# DRV8848.net
KiCad netlist of a schematic drawn in EAGLE
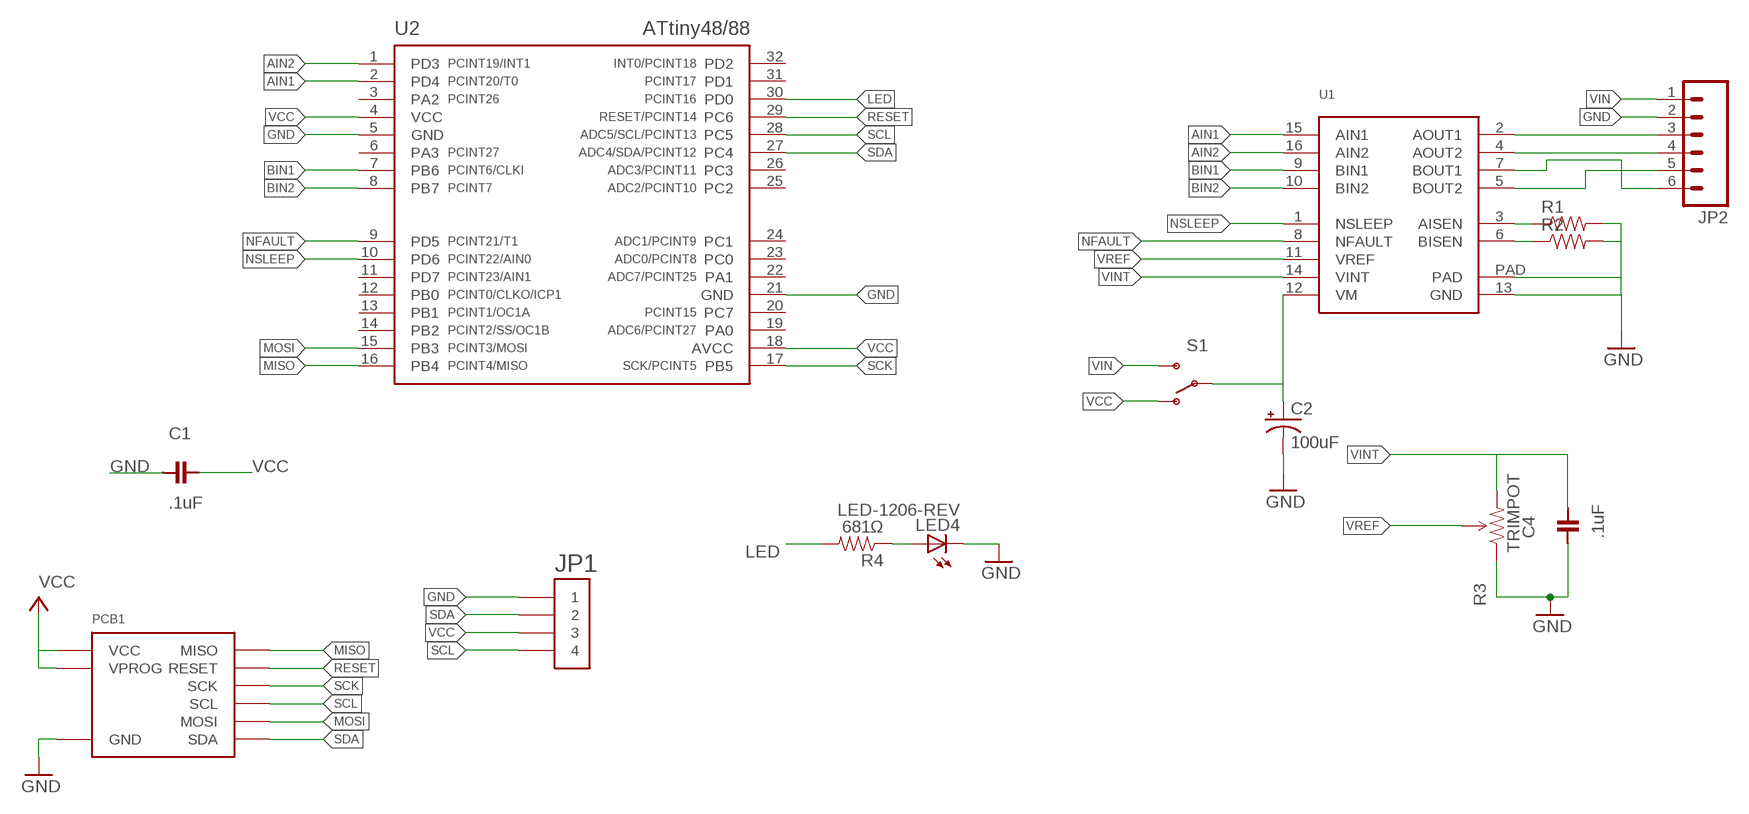
[diagram p0: schematic, sheet 1]

(export (version "E")
  (design (tool "Eeschema 10.0.6"))
  (components
    (comp (ref "C1")
      (value ".1uF")
      (footprint "eagle-import:0603")
      (fields (field (name "PARTNUM") "C0603C104K5RACTU"))
      (libsource (lib "eagle-import") (part "CAPACITOR-.1UF"))
    )
    (comp (ref "C2")
      (value "100uF")
      (footprint "eagle-import:PANASONIC_D")
      (libsource (lib "eagle-import") (part "CAP_POLD"))
    )
    (comp (ref "C4")
      (value ".1uF")
      (footprint "eagle-import:0603")
      (fields (field (name "PARTNUM") "C0603C104K5RACTU"))
      (libsource (lib "eagle-import") (part "CAPACITOR-.1UF"))
    )
    (comp (ref "JP1")
      (value "HEADER-1X4-AMPMODU")
      (footprint "eagle-import:AMPMODU-4P")
      (libsource (lib "eagle-import") (part "HEADER-1X4-AMPMODU"))
    )
    (comp (ref "JP2")
      (value "M063.5MM-6")
      (footprint "eagle-import:SCREWTERMINAL-3.5MM-6")
      (libsource (lib "eagle-import") (part "M063.5MM-6"))
    )
    (comp (ref "LED4")
      (value "LED-1206-REV")
      (footprint "eagle-import:LED-1206-REV")
      (libsource (lib "eagle-import") (part "LED-1206-REV"))
    )
    (comp (ref "PCB1")
      (value "DEVICE-PCB-TABS")
      (footprint "eagle-import:DEVICE-PCB-TABS")
      (libsource (lib "eagle-import") (part "DEVICE-PCB-TABS"))
    )
    (comp (ref "R1")
      (value "RESISTOR-0603")
      (footprint "eagle-import:0603")
      (libsource (lib "eagle-import") (part "RESISTOR-0603"))
    )
    (comp (ref "R2")
      (value "RESISTOR-0603")
      (footprint "eagle-import:0603")
      (libsource (lib "eagle-import") (part "RESISTOR-0603"))
    )
    (comp (ref "R3")
      (value "TRIMPOT")
      (footprint "eagle-import:TRIMPOT-5MM-V2")
      (libsource (lib "eagle-import") (part "TRIMPOT"))
    )
    (comp (ref "R4")
      (value "681Ω")
      (footprint "eagle-import:0603")
      (fields (field (name "PARTNUM") "ERJ-3EKF6810V"))
      (libsource (lib "eagle-import") (part "RESISTOR-681Ω"))
    )
    (comp (ref "S1")
      (value "SWITCH-SPDTPTH")
      (footprint "eagle-import:SWITCH-SPDT")
      (libsource (lib "eagle-import") (part "SWITCH-SPDTPTH"))
    )
    (comp (ref "U1")
      (value "DRV8848")
      (footprint "eagle-import:HTSSOP-16")
      (libsource (lib "eagle-import") (part "DRV8848"))
    )
    (comp (ref "U2")
      (value "ATTINY48/88-TQFP")
      (footprint "eagle-import:TQFP-32")
      (libsource (lib "eagle-import") (part "ATTINY48/88-TQFP"))
    )
  )
  (nets
    (net (code "1") (name "AIN1") (class "Default")
      (node (ref "U1") (pin "15") (pinfunction "AIN1_15") (pintype "bidirectional"))
      (node (ref "U2") (pin "2") (pinfunction "PD4_2") (pintype "bidirectional"))
    )
    (net (code "2") (name "AIN2") (class "Default")
      (node (ref "U1") (pin "16") (pinfunction "AIN2_16") (pintype "bidirectional"))
      (node (ref "U2") (pin "1") (pinfunction "PD3_1") (pintype "bidirectional"))
    )
    (net (code "3") (name "BIN1") (class "Default")
      (node (ref "U1") (pin "9") (pinfunction "BIN1_9") (pintype "bidirectional"))
      (node (ref "U2") (pin "7") (pinfunction "PB6_7") (pintype "bidirectional"))
    )
    (net (code "4") (name "BIN2") (class "Default")
      (node (ref "U1") (pin "10") (pinfunction "BIN2_10") (pintype "bidirectional"))
      (node (ref "U2") (pin "8") (pinfunction "PB7_8") (pintype "bidirectional"))
    )
    (net (code "5") (name "GND") (class "Default")
      (node (ref "C1") (pin "2") (pinfunction "2_2") (pintype "passive"))
      (node (ref "C2") (pin "-") (pinfunction "-_-") (pintype "passive"))
      (node (ref "C4") (pin "2") (pinfunction "2_2") (pintype "passive"))
      (node (ref "JP1") (pin "P$1") (pinfunction "1_P$1") (pintype "bidirectional"))
      (node (ref "JP1") (pin "P$2") (pinfunction "1_P$2") (pintype "bidirectional"))
      (node (ref "JP2") (pin "2") (pinfunction "2_2") (pintype "passive"))
      (node (ref "LED4") (pin "C") (pinfunction "C_C") (pintype "passive"))
      (node (ref "PCB1") (pin "GND") (pinfunction "GND_GND") (pintype "bidirectional"))
      (node (ref "PCB1") (pin "GND1") (pinfunction "GND_GND1") (pintype "bidirectional"))
      (node (ref "R1") (pin "2") (pinfunction "2_2") (pintype "passive"))
      (node (ref "R2") (pin "2") (pinfunction "2_2") (pintype "passive"))
      (node (ref "R3") (pin "A") (pinfunction "CCW_A") (pintype "passive"))
      (node (ref "U1") (pin "13") (pinfunction "GND_13") (pintype "bidirectional"))
      (node (ref "U1") (pin "PAD") (pinfunction "PAD_PAD") (pintype "bidirectional"))
      (node (ref "U2") (pin "21") (pinfunction "GND_21") (pintype "bidirectional"))
      (node (ref "U2") (pin "5") (pinfunction "GND_5") (pintype "bidirectional"))
    )
    (net (code "6") (name "LED") (class "Default")
      (node (ref "R4") (pin "2") (pinfunction "2_2") (pintype "passive"))
      (node (ref "U2") (pin "30") (pinfunction "PD0_30") (pintype "bidirectional"))
    )
    (net (code "7") (name "MISO") (class "Default")
      (node (ref "PCB1") (pin "MISO") (pinfunction "MISO_MISO") (pintype "bidirectional"))
      (node (ref "PCB1") (pin "MISO1") (pinfunction "MISO_MISO1") (pintype "bidirectional"))
      (node (ref "U2") (pin "16") (pinfunction "PB4_16") (pintype "bidirectional"))
    )
    (net (code "8") (name "MOSI") (class "Default")
      (node (ref "PCB1") (pin "MOSI") (pinfunction "MOSI_MOSI") (pintype "bidirectional"))
      (node (ref "PCB1") (pin "MOSI1") (pinfunction "MOSI_MOSI1") (pintype "bidirectional"))
      (node (ref "U2") (pin "15") (pinfunction "PB3_15") (pintype "bidirectional"))
    )
    (net (code "9") (name "NFAULT") (class "Default")
      (node (ref "U1") (pin "8") (pinfunction "NFAULT_8") (pintype "bidirectional"))
      (node (ref "U2") (pin "9") (pinfunction "PD5_9") (pintype "bidirectional"))
    )
    (net (code "10") (name "NSLEEP") (class "Default")
      (node (ref "U1") (pin "1") (pinfunction "NSLEEP_1") (pintype "bidirectional"))
      (node (ref "U2") (pin "10") (pinfunction "PD6_10") (pintype "bidirectional"))
    )
    (net (code "11") (name "Net-(LED4-PadA)") (class "Default")
      (node (ref "LED4") (pin "A") (pinfunction "A_A") (pintype "passive"))
      (node (ref "R4") (pin "1") (pinfunction "1_1") (pintype "passive"))
    )
    (net (code "12") (name "Net-(S1-P)") (class "Default")
      (node (ref "C2") (pin "+") (pinfunction "+_+") (pintype "passive"))
      (node (ref "S1") (pin "2") (pinfunction "P_2") (pintype "passive"))
      (node (ref "U1") (pin "12") (pinfunction "VM_12") (pintype "bidirectional"))
    )
    (net (code "13") (name "Net-(U1-AISEN)") (class "Default")
      (node (ref "R1") (pin "1") (pinfunction "1_1") (pintype "passive"))
      (node (ref "U1") (pin "3") (pinfunction "AISEN_3") (pintype "bidirectional"))
    )
    (net (code "14") (name "Net-(U1-AOUT1)") (class "Default")
      (node (ref "JP2") (pin "3") (pinfunction "3_3") (pintype "passive"))
      (node (ref "U1") (pin "2") (pinfunction "AOUT1_2") (pintype "bidirectional"))
    )
    (net (code "15") (name "Net-(U1-AOUT2)") (class "Default")
      (node (ref "JP2") (pin "4") (pinfunction "4_4") (pintype "passive"))
      (node (ref "U1") (pin "4") (pinfunction "AOUT2_4") (pintype "bidirectional"))
    )
    (net (code "16") (name "Net-(U1-BISEN)") (class "Default")
      (node (ref "R2") (pin "1") (pinfunction "1_1") (pintype "passive"))
      (node (ref "U1") (pin "6") (pinfunction "BISEN_6") (pintype "bidirectional"))
    )
    (net (code "17") (name "Net-(U1-BOUT1)") (class "Default")
      (node (ref "JP2") (pin "6") (pinfunction "6_6") (pintype "passive"))
      (node (ref "U1") (pin "7") (pinfunction "BOUT1_7") (pintype "bidirectional"))
    )
    (net (code "18") (name "Net-(U1-BOUT2)") (class "Default")
      (node (ref "JP2") (pin "5") (pinfunction "5_5") (pintype "passive"))
      (node (ref "U1") (pin "5") (pinfunction "BOUT2_5") (pintype "bidirectional"))
    )
    (net (code "19") (name "RESET") (class "Default")
      (node (ref "PCB1") (pin "RESET") (pinfunction "RESET_RESET") (pintype "bidirectional"))
      (node (ref "PCB1") (pin "RESET1") (pinfunction "RESET_RESET1") (pintype "bidirectional"))
      (node (ref "U2") (pin "29") (pinfunction "PC6_29") (pintype "bidirectional"))
    )
    (net (code "20") (name "SCK") (class "Default")
      (node (ref "PCB1") (pin "CLK") (pinfunction "SCK_CLK") (pintype "bidirectional"))
      (node (ref "PCB1") (pin "CLK1") (pinfunction "SCK_CLK1") (pintype "bidirectional"))
      (node (ref "U2") (pin "17") (pinfunction "PB5_17") (pintype "bidirectional"))
    )
    (net (code "21") (name "SCL") (class "Default")
      (node (ref "JP1") (pin "P$7") (pinfunction "4_P$7") (pintype "bidirectional"))
      (node (ref "JP1") (pin "P$8") (pinfunction "4_P$8") (pintype "bidirectional"))
      (node (ref "PCB1") (pin "SCL") (pinfunction "SCL_SCL") (pintype "bidirectional"))
      (node (ref "PCB1") (pin "SCL1") (pinfunction "SCL_SCL1") (pintype "bidirectional"))
      (node (ref "U2") (pin "28") (pinfunction "PC5_28") (pintype "bidirectional"))
    )
    (net (code "22") (name "SDA") (class "Default")
      (node (ref "JP1") (pin "P$3") (pinfunction "2_P$3") (pintype "bidirectional"))
      (node (ref "JP1") (pin "P$4") (pinfunction "2_P$4") (pintype "bidirectional"))
      (node (ref "PCB1") (pin "SDA") (pinfunction "SDA_SDA") (pintype "bidirectional"))
      (node (ref "PCB1") (pin "SDA1") (pinfunction "SDA_SDA1") (pintype "bidirectional"))
      (node (ref "U2") (pin "27") (pinfunction "PC4_27") (pintype "bidirectional"))
    )
    (net (code "23") (name "VCC") (class "Default")
      (node (ref "C1") (pin "1") (pinfunction "1_1") (pintype "passive"))
      (node (ref "JP1") (pin "P$5") (pinfunction "3_P$5") (pintype "bidirectional"))
      (node (ref "JP1") (pin "P$6") (pinfunction "3_P$6") (pintype "bidirectional"))
      (node (ref "PCB1") (pin "VCC") (pinfunction "VCC_VCC") (pintype "bidirectional"))
      (node (ref "PCB1") (pin "VCC1") (pinfunction "VCC_VCC1") (pintype "bidirectional"))
      (node (ref "PCB1") (pin "VPROG") (pinfunction "VPROG_VPROG") (pintype "bidirectional"))
      (node (ref "PCB1") (pin "VPROG1") (pinfunction "VPROG_VPROG1") (pintype "bidirectional"))
      (node (ref "S1") (pin "1") (pinfunction "O_1") (pintype "passive"))
      (node (ref "U2") (pin "18") (pinfunction "AVCC_18") (pintype "power_in"))
      (node (ref "U2") (pin "4") (pinfunction "VCC_4") (pintype "bidirectional"))
    )
    (net (code "24") (name "VIN") (class "Default")
      (node (ref "JP2") (pin "1") (pinfunction "1_1") (pintype "passive"))
      (node (ref "S1") (pin "3") (pinfunction "S_3") (pintype "passive"))
    )
    (net (code "25") (name "VINT") (class "Default")
      (node (ref "C4") (pin "1") (pinfunction "1_1") (pintype "passive"))
      (node (ref "R3") (pin "C") (pinfunction "CW_C") (pintype "passive"))
      (node (ref "U1") (pin "14") (pinfunction "VINT_14") (pintype "bidirectional"))
    )
    (net (code "26") (name "VREF") (class "Default")
      (node (ref "R3") (pin "B") (pinfunction "WIPER_B") (pintype "passive"))
      (node (ref "U1") (pin "11") (pinfunction "VREF_11") (pintype "bidirectional"))
    )
    (net (code "27") (name "unconnected-(U2-PA0-Pad19)") (class "Default")
      (node (ref "U2") (pin "19") (pinfunction "PA0_19") (pintype "bidirectional"))
    )
    (net (code "28") (name "unconnected-(U2-PA1-Pad22)") (class "Default")
      (node (ref "U2") (pin "22") (pinfunction "PA1_22") (pintype "bidirectional"))
    )
    (net (code "29") (name "unconnected-(U2-PA2-Pad3)") (class "Default")
      (node (ref "U2") (pin "3") (pinfunction "PA2_3") (pintype "bidirectional"))
    )
    (net (code "30") (name "unconnected-(U2-PA3-Pad6)") (class "Default")
      (node (ref "U2") (pin "6") (pinfunction "PA3_6") (pintype "bidirectional"))
    )
    (net (code "31") (name "unconnected-(U2-PB0-Pad12)") (class "Default")
      (node (ref "U2") (pin "12") (pinfunction "PB0_12") (pintype "bidirectional"))
    )
    (net (code "32") (name "unconnected-(U2-PB1-Pad13)") (class "Default")
      (node (ref "U2") (pin "13") (pinfunction "PB1_13") (pintype "bidirectional"))
    )
    (net (code "33") (name "unconnected-(U2-PB2-Pad14)") (class "Default")
      (node (ref "U2") (pin "14") (pinfunction "PB2_14") (pintype "bidirectional"))
    )
    (net (code "34") (name "unconnected-(U2-PC0-Pad23)") (class "Default")
      (node (ref "U2") (pin "23") (pinfunction "PC0_23") (pintype "bidirectional"))
    )
    (net (code "35") (name "unconnected-(U2-PC1-Pad24)") (class "Default")
      (node (ref "U2") (pin "24") (pinfunction "PC1_24") (pintype "bidirectional"))
    )
    (net (code "36") (name "unconnected-(U2-PC2-Pad25)") (class "Default")
      (node (ref "U2") (pin "25") (pinfunction "PC2_25") (pintype "bidirectional"))
    )
    (net (code "37") (name "unconnected-(U2-PC3-Pad26)") (class "Default")
      (node (ref "U2") (pin "26") (pinfunction "PC3_26") (pintype "bidirectional"))
    )
    (net (code "38") (name "unconnected-(U2-PC7-Pad20)") (class "Default")
      (node (ref "U2") (pin "20") (pinfunction "PC7_20") (pintype "bidirectional"))
    )
    (net (code "39") (name "unconnected-(U2-PD1-Pad31)") (class "Default")
      (node (ref "U2") (pin "31") (pinfunction "PD1_31") (pintype "bidirectional"))
    )
    (net (code "40") (name "unconnected-(U2-PD2-Pad32)") (class "Default")
      (node (ref "U2") (pin "32") (pinfunction "PD2_32") (pintype "bidirectional"))
    )
    (net (code "41") (name "unconnected-(U2-PD7-Pad11)") (class "Default")
      (node (ref "U2") (pin "11") (pinfunction "PD7_11") (pintype "bidirectional"))
    )
  )
)
